# rc2014_z80plus.net
KiCad netlist of a schematic drawn in EAGLE
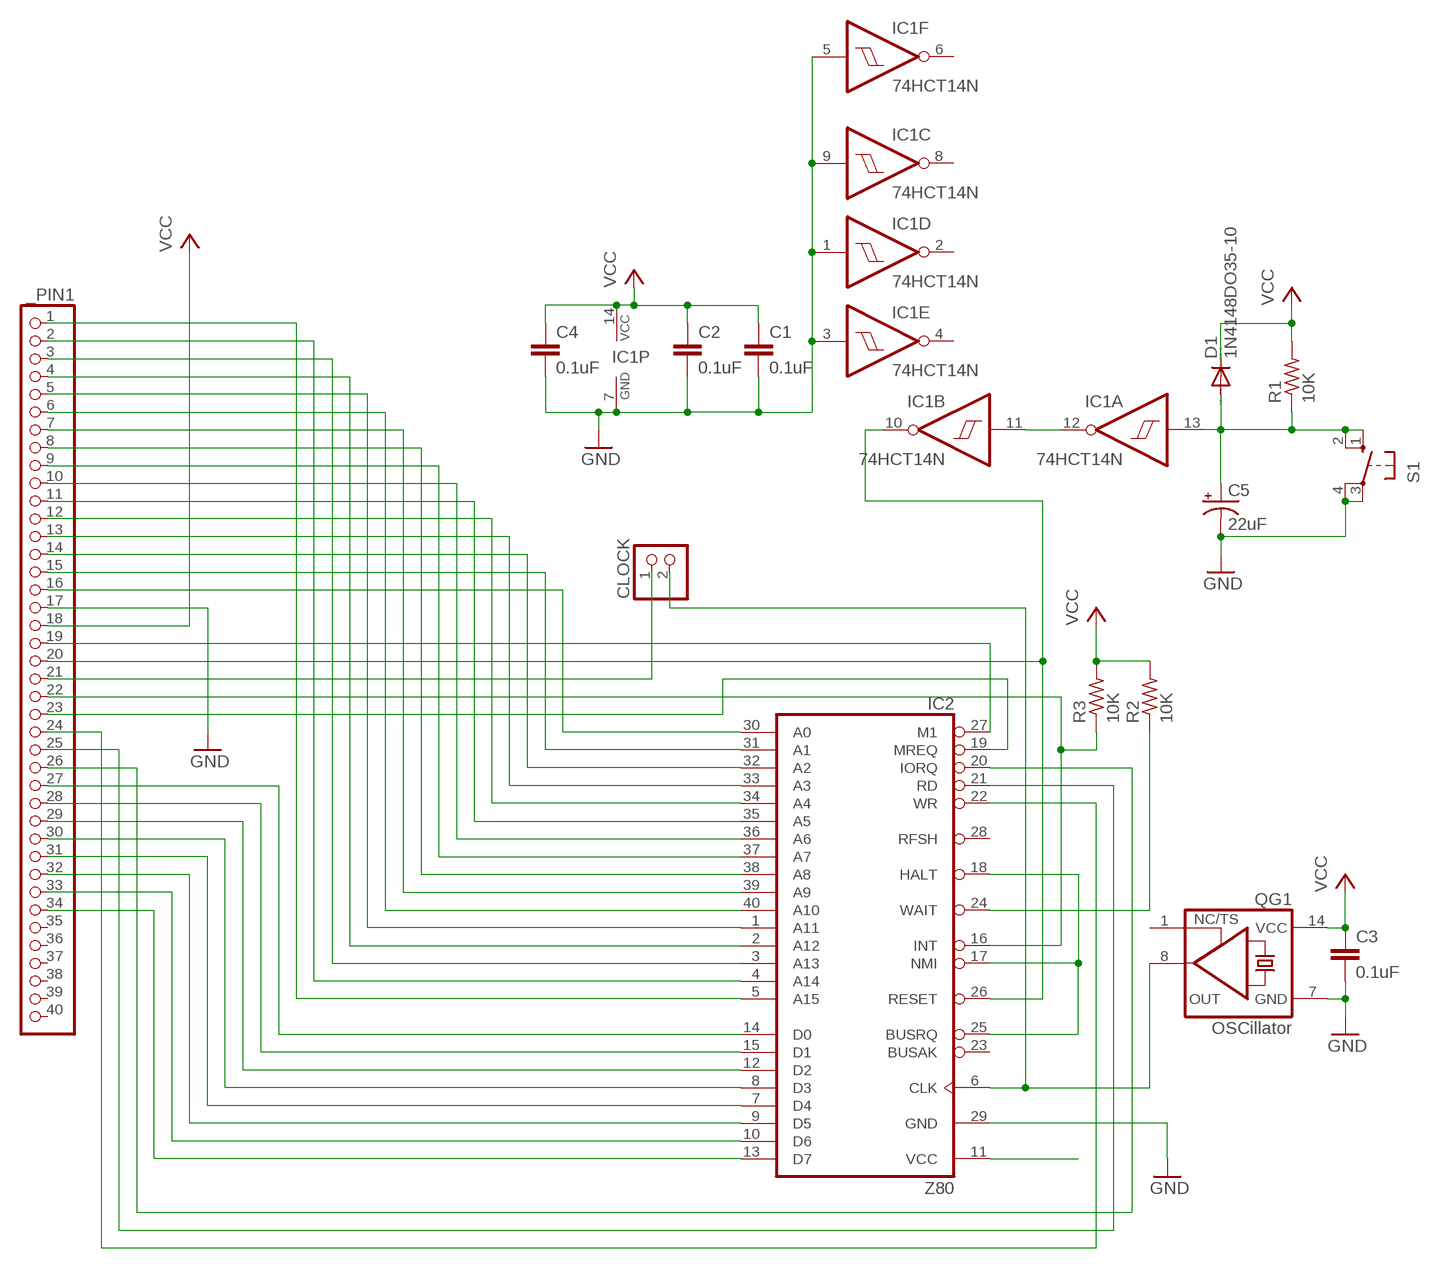
[diagram p0: schematic, sheet 1]

(export (version "E")
  (design (tool "Eeschema 10.0.6"))
  (components
    (comp (ref "C1")
      (value "0.1uF")
      (footprint "eagle-import:C050-024X044")
      (libsource (lib "eagle-import") (part "C-EU050-024X044"))
    )
    (comp (ref "C2")
      (value "0.1uF")
      (footprint "eagle-import:C050-024X044")
      (libsource (lib "eagle-import") (part "C-EU050-024X044"))
    )
    (comp (ref "C3")
      (value "0.1uF")
      (footprint "eagle-import:C050-024X044")
      (libsource (lib "eagle-import") (part "C-EU050-024X044"))
    )
    (comp (ref "C4")
      (value "0.1uF")
      (footprint "eagle-import:C050-024X044")
      (libsource (lib "eagle-import") (part "C-EU050-024X044"))
    )
    (comp (ref "C5")
      (value "22uF")
      (footprint "eagle-import:TAP5-80")
      (libsource (lib "eagle-import") (part "CPOL-USTAP5-80"))
    )
    (comp (ref "CLOCK")
      (value "PINHD-1X2")
      (footprint "eagle-import:1X02")
      (libsource (lib "eagle-import") (part "PINHD-1X2"))
    )
    (comp (ref "D1")
      (value "1N4148DO35-10")
      (footprint "eagle-import:DO35-10")
      (libsource (lib "eagle-import") (part "1N4148DO35-10"))
    )
    (comp (ref "IC1")
      (value "74HCT14N")
      (footprint "eagle-import:DIL14")
      (libsource (lib "eagle-import") (part "7414NHCT"))
    )
    (comp (ref "IC2")
      (value "Z80")
      (footprint "eagle-import:DIL40")
      (libsource (lib "eagle-import") (part "Z80CPU"))
    )
    (comp (ref "QG1")
      (value "OSCillator")
      (footprint "eagle-import:DIL14S")
      (libsource (lib "eagle-import") (part "XO-14"))
    )
    (comp (ref "R1")
      (value "10K")
      (footprint "eagle-import:0207_10")
      (libsource (lib "eagle-import") (part "R-US_0207/10"))
    )
    (comp (ref "R2")
      (value "10K")
      (footprint "eagle-import:0207_10")
      (libsource (lib "eagle-import") (part "R-US_0207/10"))
    )
    (comp (ref "R3")
      (value "10K")
      (footprint "eagle-import:0207_10")
      (libsource (lib "eagle-import") (part "R-US_0207/10"))
    )
    (comp (ref "S1")
      (value "10-XX")
      (footprint "eagle-import:B3F-10XX")
      (fields (field (name "MPN") "B3F-1000"))
      (libsource (lib "eagle-import") (part "10-XX"))
    )
    (comp (ref "_PIN1")
      (value "PINHD-1X40")
      (footprint "eagle-import:1X40")
      (libsource (lib "eagle-import") (part "PINHD-1X40"))
    )
  )
  (nets
    (net (code "1") (name "GND") (class "Default")
      (node (ref "C1") (pin "2") (pinfunction "2_2") (pintype "passive"))
      (node (ref "C2") (pin "2") (pinfunction "2_2") (pintype "passive"))
      (node (ref "C3") (pin "2") (pinfunction "2_2") (pintype "passive"))
      (node (ref "C4") (pin "2") (pinfunction "2_2") (pintype "passive"))
      (node (ref "C5") (pin "-") (pinfunction "-_-") (pintype "passive"))
      (node (ref "IC1") (pin "1") (pinfunction "I_1") (pintype "input"))
      (node (ref "IC1") (pin "3") (pinfunction "I_3") (pintype "input"))
      (node (ref "IC1") (pin "5") (pinfunction "I_5") (pintype "input"))
      (node (ref "IC1") (pin "7") (pinfunction "GND_7") (pintype "power_in"))
      (node (ref "IC1") (pin "9") (pinfunction "I_9") (pintype "input"))
      (node (ref "IC2") (pin "29") (pinfunction "GND_29") (pintype "power_in"))
      (node (ref "QG1") (pin "7") (pinfunction "GND_7") (pintype "power_in"))
      (node (ref "S1") (pin "3") (pinfunction "P_3") (pintype "passive"))
      (node (ref "S1") (pin "4") (pinfunction "P1_4") (pintype "passive"))
      (node (ref "_PIN1") (pin "17") (pinfunction "17_17") (pintype "passive"))
    )
    (net (code "2") (name "Net-(CLOCK-Pad1)") (class "Default")
      (node (ref "CLOCK") (pin "1") (pinfunction "1_1") (pintype "passive"))
      (node (ref "_PIN1") (pin "21") (pinfunction "21_21") (pintype "passive"))
    )
    (net (code "3") (name "Net-(IC1A-I)") (class "Default")
      (node (ref "C5") (pin "+") (pinfunction "+_+") (pintype "passive"))
      (node (ref "D1") (pin "A") (pinfunction "A_A") (pintype "passive"))
      (node (ref "IC1") (pin "13") (pinfunction "I_13") (pintype "input"))
      (node (ref "R1") (pin "1") (pinfunction "1_1") (pintype "passive"))
      (node (ref "S1") (pin "1") (pinfunction "S_1") (pintype "passive"))
      (node (ref "S1") (pin "2") (pinfunction "S1_2") (pintype "passive"))
    )
    (net (code "4") (name "Net-(IC1A-O)") (class "Default")
      (node (ref "IC1") (pin "11") (pinfunction "I_11") (pintype "input"))
      (node (ref "IC1") (pin "12") (pinfunction "O_12") (pintype "output"))
    )
    (net (code "5") (name "Net-(IC1B-O)") (class "Default")
      (node (ref "IC1") (pin "10") (pinfunction "O_10") (pintype "output"))
      (node (ref "IC2") (pin "26") (pinfunction "RESET_26") (pintype "input"))
      (node (ref "_PIN1") (pin "20") (pinfunction "20_20") (pintype "passive"))
    )
    (net (code "6") (name "Net-(IC2-A0)") (class "Default")
      (node (ref "IC2") (pin "30") (pinfunction "A0_30") (pintype "output"))
      (node (ref "_PIN1") (pin "16") (pinfunction "16_16") (pintype "passive"))
    )
    (net (code "7") (name "Net-(IC2-A1)") (class "Default")
      (node (ref "IC2") (pin "31") (pinfunction "A1_31") (pintype "output"))
      (node (ref "_PIN1") (pin "15") (pinfunction "15_15") (pintype "passive"))
    )
    (net (code "8") (name "Net-(IC2-A2)") (class "Default")
      (node (ref "IC2") (pin "32") (pinfunction "A2_32") (pintype "output"))
      (node (ref "_PIN1") (pin "14") (pinfunction "14_14") (pintype "passive"))
    )
    (net (code "9") (name "Net-(IC2-A3)") (class "Default")
      (node (ref "IC2") (pin "33") (pinfunction "A3_33") (pintype "output"))
      (node (ref "_PIN1") (pin "13") (pinfunction "13_13") (pintype "passive"))
    )
    (net (code "10") (name "Net-(IC2-A4)") (class "Default")
      (node (ref "IC2") (pin "34") (pinfunction "A4_34") (pintype "output"))
      (node (ref "_PIN1") (pin "12") (pinfunction "12_12") (pintype "passive"))
    )
    (net (code "11") (name "Net-(IC2-A5)") (class "Default")
      (node (ref "IC2") (pin "35") (pinfunction "A5_35") (pintype "output"))
      (node (ref "_PIN1") (pin "11") (pinfunction "11_11") (pintype "passive"))
    )
    (net (code "12") (name "Net-(IC2-A6)") (class "Default")
      (node (ref "IC2") (pin "36") (pinfunction "A6_36") (pintype "output"))
      (node (ref "_PIN1") (pin "10") (pinfunction "10_10") (pintype "passive"))
    )
    (net (code "13") (name "Net-(IC2-A7)") (class "Default")
      (node (ref "IC2") (pin "37") (pinfunction "A7_37") (pintype "output"))
      (node (ref "_PIN1") (pin "9") (pinfunction "9_9") (pintype "passive"))
    )
    (net (code "14") (name "Net-(IC2-A8)") (class "Default")
      (node (ref "IC2") (pin "38") (pinfunction "A8_38") (pintype "output"))
      (node (ref "_PIN1") (pin "8") (pinfunction "8_8") (pintype "passive"))
    )
    (net (code "15") (name "Net-(IC2-A9)") (class "Default")
      (node (ref "IC2") (pin "39") (pinfunction "A9_39") (pintype "output"))
      (node (ref "_PIN1") (pin "7") (pinfunction "7_7") (pintype "passive"))
    )
    (net (code "16") (name "Net-(IC2-A10)") (class "Default")
      (node (ref "IC2") (pin "40") (pinfunction "A10_40") (pintype "output"))
      (node (ref "_PIN1") (pin "6") (pinfunction "6_6") (pintype "passive"))
    )
    (net (code "17") (name "Net-(IC2-A11)") (class "Default")
      (node (ref "IC2") (pin "1") (pinfunction "A11_1") (pintype "output"))
      (node (ref "_PIN1") (pin "5") (pinfunction "5_5") (pintype "passive"))
    )
    (net (code "18") (name "Net-(IC2-A12)") (class "Default")
      (node (ref "IC2") (pin "2") (pinfunction "A12_2") (pintype "output"))
      (node (ref "_PIN1") (pin "4") (pinfunction "4_4") (pintype "passive"))
    )
    (net (code "19") (name "Net-(IC2-A13)") (class "Default")
      (node (ref "IC2") (pin "3") (pinfunction "A13_3") (pintype "output"))
      (node (ref "_PIN1") (pin "3") (pinfunction "3_3") (pintype "passive"))
    )
    (net (code "20") (name "Net-(IC2-A14)") (class "Default")
      (node (ref "IC2") (pin "4") (pinfunction "A14_4") (pintype "output"))
      (node (ref "_PIN1") (pin "2") (pinfunction "2_2") (pintype "passive"))
    )
    (net (code "21") (name "Net-(IC2-A15)") (class "Default")
      (node (ref "IC2") (pin "5") (pinfunction "A15_5") (pintype "output"))
      (node (ref "_PIN1") (pin "1") (pinfunction "1_1") (pintype "passive"))
    )
    (net (code "22") (name "Net-(IC2-CLK)") (class "Default")
      (node (ref "CLOCK") (pin "2") (pinfunction "2_2") (pintype "passive"))
      (node (ref "IC2") (pin "6") (pinfunction "CLK_6") (pintype "input"))
      (node (ref "QG1") (pin "8") (pinfunction "OUT_8") (pintype "output"))
    )
    (net (code "23") (name "Net-(IC2-D0)") (class "Default")
      (node (ref "IC2") (pin "14") (pinfunction "D0_14") (pintype "bidirectional"))
      (node (ref "_PIN1") (pin "27") (pinfunction "27_27") (pintype "passive"))
    )
    (net (code "24") (name "Net-(IC2-D1)") (class "Default")
      (node (ref "IC2") (pin "15") (pinfunction "D1_15") (pintype "bidirectional"))
      (node (ref "_PIN1") (pin "28") (pinfunction "28_28") (pintype "passive"))
    )
    (net (code "25") (name "Net-(IC2-D2)") (class "Default")
      (node (ref "IC2") (pin "12") (pinfunction "D2_12") (pintype "bidirectional"))
      (node (ref "_PIN1") (pin "29") (pinfunction "29_29") (pintype "passive"))
    )
    (net (code "26") (name "Net-(IC2-D3)") (class "Default")
      (node (ref "IC2") (pin "8") (pinfunction "D3_8") (pintype "bidirectional"))
      (node (ref "_PIN1") (pin "30") (pinfunction "30_30") (pintype "passive"))
    )
    (net (code "27") (name "Net-(IC2-D4)") (class "Default")
      (node (ref "IC2") (pin "7") (pinfunction "D4_7") (pintype "bidirectional"))
      (node (ref "_PIN1") (pin "31") (pinfunction "31_31") (pintype "passive"))
    )
    (net (code "28") (name "Net-(IC2-D5)") (class "Default")
      (node (ref "IC2") (pin "9") (pinfunction "D5_9") (pintype "bidirectional"))
      (node (ref "_PIN1") (pin "32") (pinfunction "32_32") (pintype "passive"))
    )
    (net (code "29") (name "Net-(IC2-D6)") (class "Default")
      (node (ref "IC2") (pin "10") (pinfunction "D6_10") (pintype "bidirectional"))
      (node (ref "_PIN1") (pin "33") (pinfunction "33_33") (pintype "passive"))
    )
    (net (code "30") (name "Net-(IC2-D7)") (class "Default")
      (node (ref "IC2") (pin "13") (pinfunction "D7_13") (pintype "bidirectional"))
      (node (ref "_PIN1") (pin "34") (pinfunction "34_34") (pintype "passive"))
    )
    (net (code "31") (name "Net-(IC2-INT)") (class "Default")
      (node (ref "IC2") (pin "16") (pinfunction "INT_16") (pintype "input"))
      (node (ref "R3") (pin "1") (pinfunction "1_1") (pintype "passive"))
      (node (ref "_PIN1") (pin "22") (pinfunction "22_22") (pintype "passive"))
    )
    (net (code "32") (name "Net-(IC2-IORQ)") (class "Default")
      (node (ref "IC2") (pin "20") (pinfunction "IORQ_20") (pintype "output"))
      (node (ref "_PIN1") (pin "26") (pinfunction "26_26") (pintype "passive"))
    )
    (net (code "33") (name "Net-(IC2-M1)") (class "Default")
      (node (ref "IC2") (pin "27") (pinfunction "M1_27") (pintype "output"))
      (node (ref "_PIN1") (pin "19") (pinfunction "19_19") (pintype "passive"))
    )
    (net (code "34") (name "Net-(IC2-MREQ)") (class "Default")
      (node (ref "IC2") (pin "19") (pinfunction "MREQ_19") (pintype "output"))
      (node (ref "_PIN1") (pin "23") (pinfunction "23_23") (pintype "passive"))
    )
    (net (code "35") (name "Net-(IC2-RD)") (class "Default")
      (node (ref "IC2") (pin "21") (pinfunction "RD_21") (pintype "output"))
      (node (ref "_PIN1") (pin "25") (pinfunction "25_25") (pintype "passive"))
    )
    (net (code "36") (name "Net-(IC2-WAIT)") (class "Default")
      (node (ref "IC2") (pin "24") (pinfunction "WAIT_24") (pintype "input"))
      (node (ref "R2") (pin "1") (pinfunction "1_1") (pintype "passive"))
    )
    (net (code "37") (name "Net-(IC2-WR)") (class "Default")
      (node (ref "IC2") (pin "22") (pinfunction "WR_22") (pintype "output"))
      (node (ref "_PIN1") (pin "24") (pinfunction "24_24") (pintype "passive"))
    )
    (net (code "38") (name "VCC") (class "Default")
      (node (ref "C1") (pin "1") (pinfunction "1_1") (pintype "passive"))
      (node (ref "C2") (pin "1") (pinfunction "1_1") (pintype "passive"))
      (node (ref "C3") (pin "1") (pinfunction "1_1") (pintype "passive"))
      (node (ref "C4") (pin "1") (pinfunction "1_1") (pintype "passive"))
      (node (ref "D1") (pin "C") (pinfunction "C_C") (pintype "passive"))
      (node (ref "IC1") (pin "14") (pinfunction "VCC_14") (pintype "power_in"))
      (node (ref "IC2") (pin "11") (pinfunction "VCC_11") (pintype "power_in"))
      (node (ref "IC2") (pin "17") (pinfunction "NMI_17") (pintype "input"))
      (node (ref "IC2") (pin "18") (pinfunction "HALT_18") (pintype "output"))
      (node (ref "IC2") (pin "25") (pinfunction "BUSRQ_25") (pintype "input"))
      (node (ref "QG1") (pin "14") (pinfunction "VCC_14") (pintype "power_in"))
      (node (ref "R1") (pin "2") (pinfunction "2_2") (pintype "passive"))
      (node (ref "R2") (pin "2") (pinfunction "2_2") (pintype "passive"))
      (node (ref "R3") (pin "2") (pinfunction "2_2") (pintype "passive"))
      (node (ref "_PIN1") (pin "18") (pinfunction "18_18") (pintype "passive"))
    )
    (net (code "39") (name "unconnected-(IC1C-O-Pad8)") (class "Default")
      (node (ref "IC1") (pin "8") (pinfunction "O_8") (pintype "output"))
    )
    (net (code "40") (name "unconnected-(IC1D-O-Pad2)") (class "Default")
      (node (ref "IC1") (pin "2") (pinfunction "O_2") (pintype "output"))
    )
    (net (code "41") (name "unconnected-(IC1E-O-Pad4)") (class "Default")
      (node (ref "IC1") (pin "4") (pinfunction "O_4") (pintype "output"))
    )
    (net (code "42") (name "unconnected-(IC1F-O-Pad6)") (class "Default")
      (node (ref "IC1") (pin "6") (pinfunction "O_6") (pintype "output"))
    )
    (net (code "43") (name "unconnected-(IC2-BUSAK-Pad23)") (class "Default")
      (node (ref "IC2") (pin "23") (pinfunction "BUSAK_23") (pintype "output"))
    )
    (net (code "44") (name "unconnected-(IC2-RFSH-Pad28)") (class "Default")
      (node (ref "IC2") (pin "28") (pinfunction "RFSH_28") (pintype "output"))
    )
    (net (code "45") (name "unconnected-(QG1-TS-Pad1)") (class "Default")
      (node (ref "QG1") (pin "1") (pinfunction "TS_1") (pintype "passive"))
    )
    (net (code "46") (name "unconnected-(_PIN1-Pad35)") (class "Default")
      (node (ref "_PIN1") (pin "35") (pinfunction "35_35") (pintype "passive"))
    )
    (net (code "47") (name "unconnected-(_PIN1-Pad36)") (class "Default")
      (node (ref "_PIN1") (pin "36") (pinfunction "36_36") (pintype "passive"))
    )
    (net (code "48") (name "unconnected-(_PIN1-Pad37)") (class "Default")
      (node (ref "_PIN1") (pin "37") (pinfunction "37_37") (pintype "passive"))
    )
    (net (code "49") (name "unconnected-(_PIN1-Pad38)") (class "Default")
      (node (ref "_PIN1") (pin "38") (pinfunction "38_38") (pintype "passive"))
    )
    (net (code "50") (name "unconnected-(_PIN1-Pad39)") (class "Default")
      (node (ref "_PIN1") (pin "39") (pinfunction "39_39") (pintype "passive"))
    )
    (net (code "51") (name "unconnected-(_PIN1-Pad40)") (class "Default")
      (node (ref "_PIN1") (pin "40") (pinfunction "40_40") (pintype "passive"))
    )
  )
)
